# LED_assembly.net
KiCad netlist of a schematic drawn in EAGLE
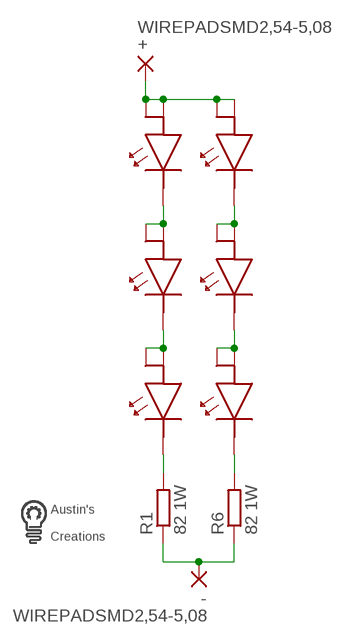
[diagram p0: schematic, sheet 1]

(export (version "E")
  (design (tool "Eeschema 10.0.6"))
  (components
    (comp (ref "+")
      (value "WIREPADSMD2,54-5,08")
      (footprint "eagle-import:SMD2,54-5,08")
      (libsource (lib "eagle-import") (part "WIREPADSMD2,54-5,08"))
    )
    (comp (ref "-")
      (value "WIREPADSMD2,54-5,08")
      (footprint "eagle-import:SMD2,54-5,08")
      (libsource (lib "eagle-import") (part "WIREPADSMD2,54-5,08"))
    )
    (comp (ref "R1")
      (value "82 1W")
      (footprint "eagle-import:R2010")
      (libsource (lib "eagle-import") (part "R-EU_R2010"))
    )
    (comp (ref "R6")
      (value "82 1W")
      (footprint "eagle-import:R2010")
      (libsource (lib "eagle-import") (part "R-EU_R2010"))
    )
    (comp (ref "U$1")
      (value "LOGOMED")
      (footprint "eagle-import:LOGOMED")
      (libsource (lib "eagle-import") (part "LOGOMED"))
    )
    (comp (ref "U$6")
      (value "5730LED")
      (footprint "eagle-import:5730LED")
      (libsource (lib "eagle-import") (part "5730LED"))
    )
    (comp (ref "U$7")
      (value "5730LED")
      (footprint "eagle-import:5730LED")
      (libsource (lib "eagle-import") (part "5730LED"))
    )
    (comp (ref "U$8")
      (value "5730LED")
      (footprint "eagle-import:5730LED")
      (libsource (lib "eagle-import") (part "5730LED"))
    )
    (comp (ref "U$23")
      (value "5730LED")
      (footprint "eagle-import:5730LED")
      (libsource (lib "eagle-import") (part "5730LED"))
    )
    (comp (ref "U$24")
      (value "5730LED")
      (footprint "eagle-import:5730LED")
      (libsource (lib "eagle-import") (part "5730LED"))
    )
    (comp (ref "U$25")
      (value "5730LED")
      (footprint "eagle-import:5730LED")
      (libsource (lib "eagle-import") (part "5730LED"))
    )
  )
  (nets
    (net (code "1") (name "Net-(+-P)") (class "Default")
      (node (ref "+") (pin "1") (pinfunction "P_1") (pintype "passive"))
      (node (ref "U$23") (pin "P$1") (pinfunction "P$1_P$1") (pintype "bidirectional"))
      (node (ref "U$23") (pin "P$3") (pinfunction "P$3_P$3") (pintype "bidirectional"))
      (node (ref "U$6") (pin "P$1") (pinfunction "P$1_P$1") (pintype "bidirectional"))
      (node (ref "U$6") (pin "P$3") (pinfunction "P$3_P$3") (pintype "bidirectional"))
    )
    (net (code "2") (name "Net-(--P)") (class "Default")
      (node (ref "-") (pin "1") (pinfunction "P_1") (pintype "passive"))
      (node (ref "R1") (pin "1") (pinfunction "1_1") (pintype "passive"))
      (node (ref "R6") (pin "1") (pinfunction "1_1") (pintype "passive"))
    )
    (net (code "3") (name "Net-(R1-Pad2)") (class "Default")
      (node (ref "R1") (pin "2") (pinfunction "2_2") (pintype "passive"))
      (node (ref "U$8") (pin "P$2") (pinfunction "P$2_P$2") (pintype "bidirectional"))
    )
    (net (code "4") (name "Net-(R6-Pad2)") (class "Default")
      (node (ref "R6") (pin "2") (pinfunction "2_2") (pintype "passive"))
      (node (ref "U$25") (pin "P$2") (pinfunction "P$2_P$2") (pintype "bidirectional"))
    )
    (net (code "5") (name "Net-(U$6-PadP$2)") (class "Default")
      (node (ref "U$6") (pin "P$2") (pinfunction "P$2_P$2") (pintype "bidirectional"))
      (node (ref "U$7") (pin "P$1") (pinfunction "P$1_P$1") (pintype "bidirectional"))
      (node (ref "U$7") (pin "P$3") (pinfunction "P$3_P$3") (pintype "bidirectional"))
    )
    (net (code "6") (name "Net-(U$7-PadP$2)") (class "Default")
      (node (ref "U$7") (pin "P$2") (pinfunction "P$2_P$2") (pintype "bidirectional"))
      (node (ref "U$8") (pin "P$1") (pinfunction "P$1_P$1") (pintype "bidirectional"))
      (node (ref "U$8") (pin "P$3") (pinfunction "P$3_P$3") (pintype "bidirectional"))
    )
    (net (code "7") (name "Net-(U$23-PadP$2)") (class "Default")
      (node (ref "U$23") (pin "P$2") (pinfunction "P$2_P$2") (pintype "bidirectional"))
      (node (ref "U$24") (pin "P$1") (pinfunction "P$1_P$1") (pintype "bidirectional"))
      (node (ref "U$24") (pin "P$3") (pinfunction "P$3_P$3") (pintype "bidirectional"))
    )
    (net (code "8") (name "Net-(U$24-PadP$2)") (class "Default")
      (node (ref "U$24") (pin "P$2") (pinfunction "P$2_P$2") (pintype "bidirectional"))
      (node (ref "U$25") (pin "P$1") (pinfunction "P$1_P$1") (pintype "bidirectional"))
      (node (ref "U$25") (pin "P$3") (pinfunction "P$3_P$3") (pintype "bidirectional"))
    )
  )
)
